# alphanewt_v0_1.net
KiCad netlist of a schematic drawn in EAGLE
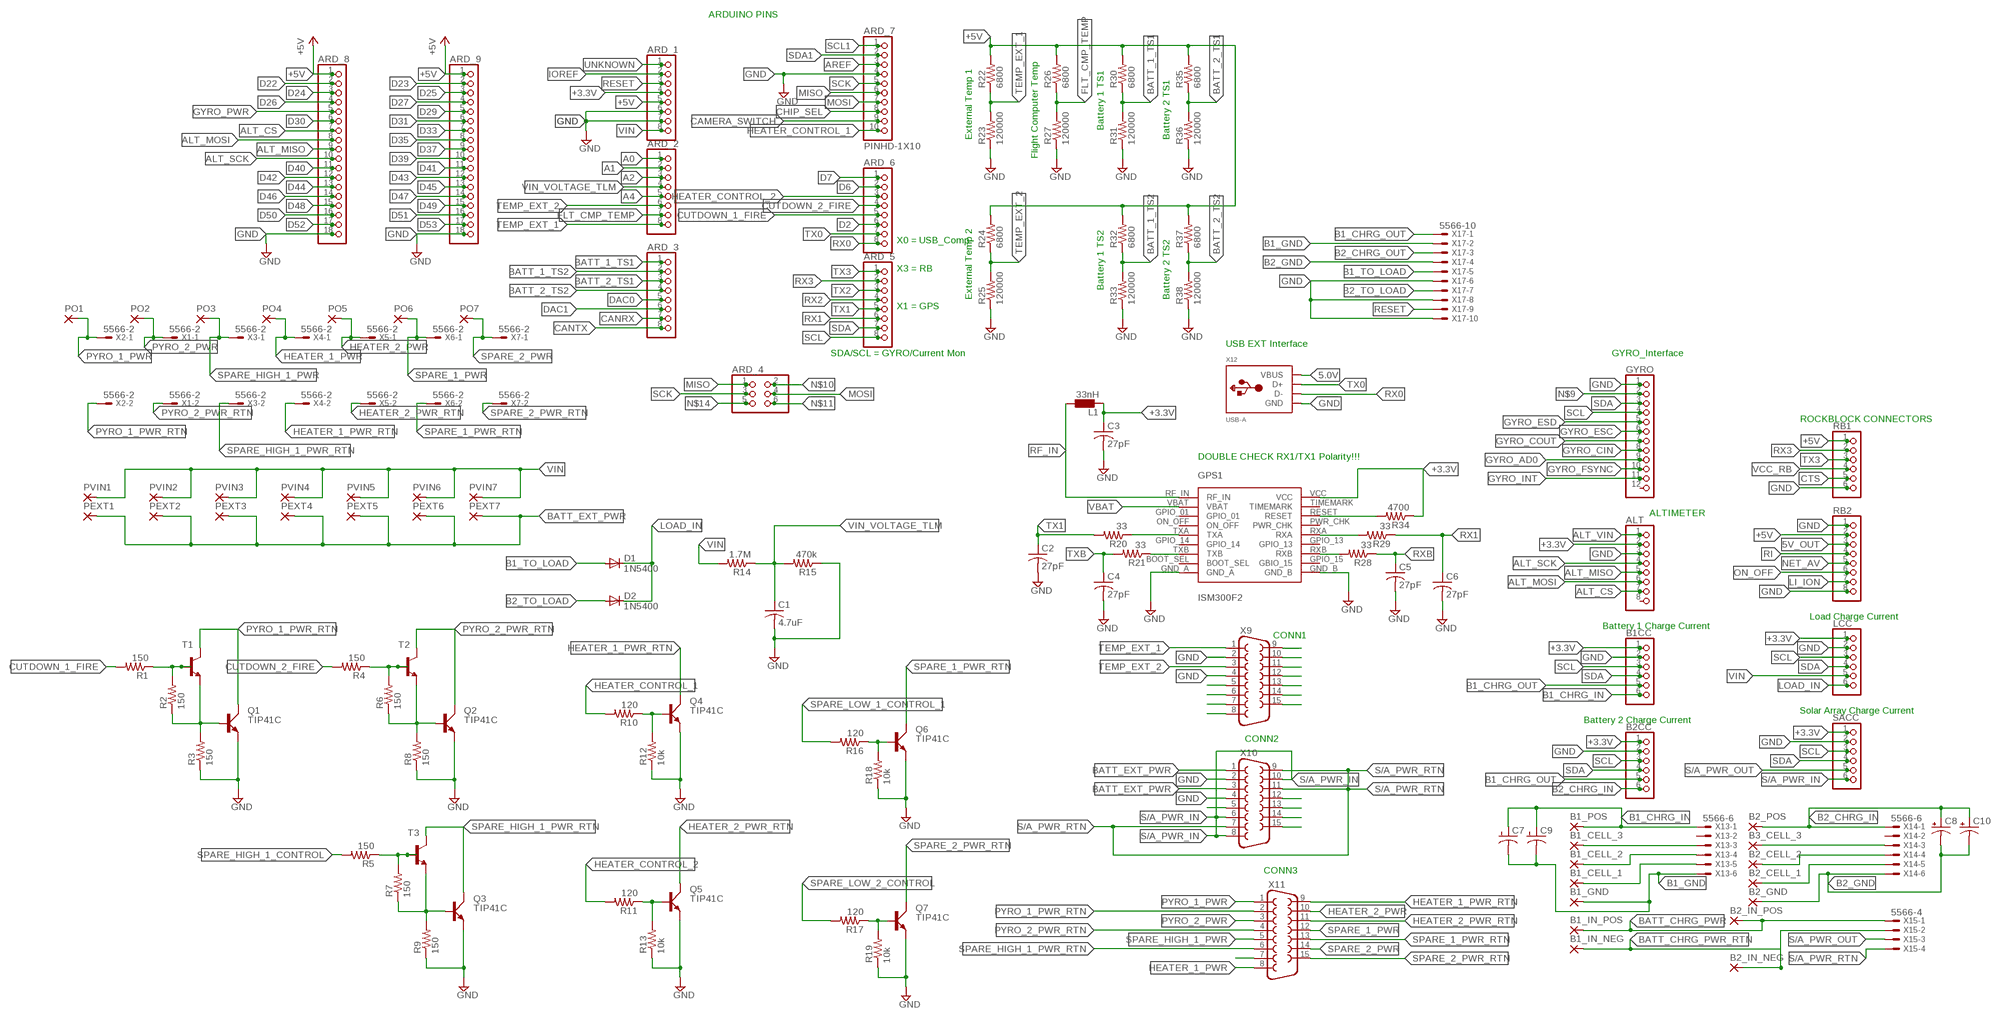
[diagram p0: schematic, sheet 1]

(export (version "E")
  (design (tool "Eeschema 10.0.6"))
  (components
    (comp (ref "ALT")
      (value "PINHD-1X8BIG")
      (footprint "eagle-import:1X08-BIG")
      (libsource (lib "eagle-import") (part "PINHD-1X8BIG"))
    )
    (comp (ref "ARD_1")
      (value "PINHD-1X8BIG")
      (footprint "eagle-import:1X08-BIG")
      (libsource (lib "eagle-import") (part "PINHD-1X8BIG"))
    )
    (comp (ref "ARD_2")
      (value "PINHD-1X8BIG")
      (footprint "eagle-import:1X08-BIG")
      (libsource (lib "eagle-import") (part "PINHD-1X8BIG"))
    )
    (comp (ref "ARD_3")
      (value "PINHD-1X8BIG")
      (footprint "eagle-import:1X08-BIG")
      (libsource (lib "eagle-import") (part "PINHD-1X8BIG"))
    )
    (comp (ref "ARD_4")
      (value "PINHD-2X3")
      (footprint "eagle-import:2X03")
      (libsource (lib "eagle-import") (part "PINHD-2X3"))
    )
    (comp (ref "ARD_5")
      (value "PINHD-1X8BIG")
      (footprint "eagle-import:1X08-BIG")
      (libsource (lib "eagle-import") (part "PINHD-1X8BIG"))
    )
    (comp (ref "ARD_6")
      (value "PINHD-1X8BIG")
      (footprint "eagle-import:1X08-BIG")
      (libsource (lib "eagle-import") (part "PINHD-1X8BIG"))
    )
    (comp (ref "ARD_7")
      (value "PINHD-1X10")
      (footprint "eagle-import:1X10-BIG")
      (libsource (lib "eagle-import") (part "PINHD-1X10"))
    )
    (comp (ref "ARD_8")
      (value "PINHD-1X18-BIG")
      (footprint "eagle-import:1X18-BIG")
      (libsource (lib "eagle-import") (part "PINHD-1X18-BIG"))
    )
    (comp (ref "ARD_9")
      (value "PINHD-1X18-BIG")
      (footprint "eagle-import:1X18-BIG")
      (libsource (lib "eagle-import") (part "PINHD-1X18-BIG"))
    )
    (comp (ref "B1CC")
      (value "PINHD-1X6B")
      (footprint "eagle-import:1X06-BIG")
      (libsource (lib "eagle-import") (part "PINHD-1X6B"))
    )
    (comp (ref "B1_CELL_1")
      (value "SMD5")
      (footprint "eagle-import:SMD2,54-5,08")
      (libsource (lib "eagle-import") (part "SMD5"))
    )
    (comp (ref "B1_CELL_2")
      (value "SMD5")
      (footprint "eagle-import:SMD2,54-5,08")
      (libsource (lib "eagle-import") (part "SMD5"))
    )
    (comp (ref "B1_CELL_3")
      (value "SMD5")
      (footprint "eagle-import:SMD2,54-5,08")
      (libsource (lib "eagle-import") (part "SMD5"))
    )
    (comp (ref "B1_GND")
      (value "SMD5")
      (footprint "eagle-import:SMD2,54-5,08")
      (libsource (lib "eagle-import") (part "SMD5"))
    )
    (comp (ref "B1_IN_NEG")
      (value "SMD5")
      (footprint "eagle-import:SMD2,54-5,08")
      (libsource (lib "eagle-import") (part "SMD5"))
    )
    (comp (ref "B1_IN_POS")
      (value "SMD5")
      (footprint "eagle-import:SMD2,54-5,08")
      (libsource (lib "eagle-import") (part "SMD5"))
    )
    (comp (ref "B1_POS")
      (value "SMD5")
      (footprint "eagle-import:SMD2,54-5,08")
      (libsource (lib "eagle-import") (part "SMD5"))
    )
    (comp (ref "B2CC")
      (value "PINHD-1X6B")
      (footprint "eagle-import:1X06-BIG")
      (libsource (lib "eagle-import") (part "PINHD-1X6B"))
    )
    (comp (ref "B2_CELL_1")
      (value "SMD5")
      (footprint "eagle-import:SMD2,54-5,08")
      (libsource (lib "eagle-import") (part "SMD5"))
    )
    (comp (ref "B2_CELL_2")
      (value "SMD5")
      (footprint "eagle-import:SMD2,54-5,08")
      (libsource (lib "eagle-import") (part "SMD5"))
    )
    (comp (ref "B2_GND")
      (value "SMD5")
      (footprint "eagle-import:SMD2,54-5,08")
      (libsource (lib "eagle-import") (part "SMD5"))
    )
    (comp (ref "B2_IN_NEG")
      (value "SMD5")
      (footprint "eagle-import:SMD2,54-5,08")
      (libsource (lib "eagle-import") (part "SMD5"))
    )
    (comp (ref "B2_IN_POS")
      (value "SMD5")
      (footprint "eagle-import:SMD2,54-5,08")
      (libsource (lib "eagle-import") (part "SMD5"))
    )
    (comp (ref "B2_POS")
      (value "SMD5")
      (footprint "eagle-import:SMD2,54-5,08")
      (libsource (lib "eagle-import") (part "SMD5"))
    )
    (comp (ref "B3_CELL_3")
      (value "SMD5")
      (footprint "eagle-import:SMD2,54-5,08")
      (libsource (lib "eagle-import") (part "SMD5"))
    )
    (comp (ref "C1")
      (value "4.7uF")
      (footprint "eagle-import:C0805K")
      (fields (field (name "MPN") "C0805C270J5GACTU"))
      (libsource (lib "eagle-import") (part "C-USC0805K"))
    )
    (comp (ref "C2")
      (value "27pF")
      (footprint "eagle-import:C0805K")
      (fields (field (name "MPN") "C0805C270J5GACTU"))
      (libsource (lib "eagle-import") (part "C-USC0805K"))
    )
    (comp (ref "C3")
      (value "27pF")
      (footprint "eagle-import:C0805K")
      (fields (field (name "MPN") "C0805C270J5GACTU"))
      (libsource (lib "eagle-import") (part "C-USC0805K"))
    )
    (comp (ref "C4")
      (value "27pF")
      (footprint "eagle-import:C0805K")
      (fields (field (name "MPN") "C0805C270J5GACTU"))
      (libsource (lib "eagle-import") (part "C-USC0805K"))
    )
    (comp (ref "C5")
      (value "27pF")
      (footprint "eagle-import:C0805K")
      (fields (field (name "MPN") "C0805C270J5GACTU"))
      (libsource (lib "eagle-import") (part "C-USC0805K"))
    )
    (comp (ref "C6")
      (value "27pF")
      (footprint "eagle-import:C0805K")
      (fields (field (name "MPN") "C0805C270J5GACTU"))
      (libsource (lib "eagle-import") (part "C-USC0805K"))
    )
    (comp (ref "C7")
      (value "CPOL-USCT7343")
      (footprint "eagle-import:CT7343")
      (libsource (lib "eagle-import") (part "CPOL-USCT7343"))
    )
    (comp (ref "C8")
      (value "CPOL-USCT7343")
      (footprint "eagle-import:CT7343")
      (libsource (lib "eagle-import") (part "CPOL-USCT7343"))
    )
    (comp (ref "C9")
      (value "CPOL-USCT7343")
      (footprint "eagle-import:CT7343")
      (libsource (lib "eagle-import") (part "CPOL-USCT7343"))
    )
    (comp (ref "C10")
      (value "CPOL-USCT7343")
      (footprint "eagle-import:CT7343")
      (libsource (lib "eagle-import") (part "CPOL-USCT7343"))
    )
    (comp (ref "D1")
      (value "1N5400")
      (footprint "eagle-import:DO201-15")
      (libsource (lib "eagle-import") (part "1N5400"))
    )
    (comp (ref "D2")
      (value "1N5400")
      (footprint "eagle-import:DO201-15")
      (libsource (lib "eagle-import") (part "1N5400"))
    )
    (comp (ref "GPS1")
      (value "ISM300F2")
      (footprint "eagle-import:ISM300F2")
      (libsource (lib "eagle-import") (part "ISM300F2"))
    )
    (comp (ref "GYRO")
      (value "PINHD-1X12-CB")
      (footprint "eagle-import:1X12-CB")
      (libsource (lib "eagle-import") (part "PINHD-1X12-CB"))
    )
    (comp (ref "L1")
      (value "33nH")
      (footprint "eagle-import:L4532P")
      (fields (field (name "MPN") "MCWL06KT33N"))
      (libsource (lib "eagle-import") (part "LL4532P"))
    )
    (comp (ref "LCC")
      (value "PINHD-1X6B")
      (footprint "eagle-import:1X06-BIG")
      (libsource (lib "eagle-import") (part "PINHD-1X6B"))
    )
    (comp (ref "PEXT1")
      (value "SMD2")
      (footprint "eagle-import:SMD1,27-2,54")
      (libsource (lib "eagle-import") (part "SMD2"))
    )
    (comp (ref "PEXT2")
      (value "SMD2")
      (footprint "eagle-import:SMD1,27-2,54")
      (libsource (lib "eagle-import") (part "SMD2"))
    )
    (comp (ref "PEXT3")
      (value "SMD2")
      (footprint "eagle-import:SMD1,27-2,54")
      (libsource (lib "eagle-import") (part "SMD2"))
    )
    (comp (ref "PEXT4")
      (value "SMD2")
      (footprint "eagle-import:SMD1,27-2,54")
      (libsource (lib "eagle-import") (part "SMD2"))
    )
    (comp (ref "PEXT5")
      (value "SMD2")
      (footprint "eagle-import:SMD1,27-2,54")
      (libsource (lib "eagle-import") (part "SMD2"))
    )
    (comp (ref "PEXT6")
      (value "SMD2")
      (footprint "eagle-import:SMD1,27-2,54")
      (libsource (lib "eagle-import") (part "SMD2"))
    )
    (comp (ref "PEXT7")
      (value "SMD2")
      (footprint "eagle-import:SMD1,27-2,54")
      (libsource (lib "eagle-import") (part "SMD2"))
    )
    (comp (ref "PO1")
      (value "SMD2")
      (footprint "eagle-import:SMD1,27-2,54")
      (libsource (lib "eagle-import") (part "SMD2"))
    )
    (comp (ref "PO2")
      (value "SMD2")
      (footprint "eagle-import:SMD1,27-2,54")
      (libsource (lib "eagle-import") (part "SMD2"))
    )
    (comp (ref "PO3")
      (value "SMD2")
      (footprint "eagle-import:SMD1,27-2,54")
      (libsource (lib "eagle-import") (part "SMD2"))
    )
    (comp (ref "PO4")
      (value "SMD2")
      (footprint "eagle-import:SMD1,27-2,54")
      (libsource (lib "eagle-import") (part "SMD2"))
    )
    (comp (ref "PO5")
      (value "SMD2")
      (footprint "eagle-import:SMD1,27-2,54")
      (libsource (lib "eagle-import") (part "SMD2"))
    )
    (comp (ref "PO6")
      (value "SMD2")
      (footprint "eagle-import:SMD1,27-2,54")
      (libsource (lib "eagle-import") (part "SMD2"))
    )
    (comp (ref "PO7")
      (value "SMD2")
      (footprint "eagle-import:SMD1,27-2,54")
      (libsource (lib "eagle-import") (part "SMD2"))
    )
    (comp (ref "PVIN1")
      (value "SMD2")
      (footprint "eagle-import:SMD1,27-2,54")
      (libsource (lib "eagle-import") (part "SMD2"))
    )
    (comp (ref "PVIN2")
      (value "SMD2")
      (footprint "eagle-import:SMD1,27-2,54")
      (libsource (lib "eagle-import") (part "SMD2"))
    )
    (comp (ref "PVIN3")
      (value "SMD2")
      (footprint "eagle-import:SMD1,27-2,54")
      (libsource (lib "eagle-import") (part "SMD2"))
    )
    (comp (ref "PVIN4")
      (value "SMD2")
      (footprint "eagle-import:SMD1,27-2,54")
      (libsource (lib "eagle-import") (part "SMD2"))
    )
    (comp (ref "PVIN5")
      (value "SMD2")
      (footprint "eagle-import:SMD1,27-2,54")
      (libsource (lib "eagle-import") (part "SMD2"))
    )
    (comp (ref "PVIN6")
      (value "SMD2")
      (footprint "eagle-import:SMD1,27-2,54")
      (libsource (lib "eagle-import") (part "SMD2"))
    )
    (comp (ref "PVIN7")
      (value "SMD2")
      (footprint "eagle-import:SMD1,27-2,54")
      (libsource (lib "eagle-import") (part "SMD2"))
    )
    (comp (ref "Q1")
      (value "TIP41C")
      (footprint "eagle-import:TO220AV")
      (libsource (lib "eagle-import") (part "TIP41C"))
    )
    (comp (ref "Q2")
      (value "TIP41C")
      (footprint "eagle-import:TO220AV")
      (libsource (lib "eagle-import") (part "TIP41C"))
    )
    (comp (ref "Q3")
      (value "TIP41C")
      (footprint "eagle-import:TO220AV")
      (libsource (lib "eagle-import") (part "TIP41C"))
    )
    (comp (ref "Q4")
      (value "TIP41C")
      (footprint "eagle-import:TO220AV")
      (libsource (lib "eagle-import") (part "TIP41C"))
    )
    (comp (ref "Q5")
      (value "TIP41C")
      (footprint "eagle-import:TO220AV")
      (libsource (lib "eagle-import") (part "TIP41C"))
    )
    (comp (ref "Q6")
      (value "TIP41C")
      (footprint "eagle-import:TO220AV")
      (libsource (lib "eagle-import") (part "TIP41C"))
    )
    (comp (ref "Q7")
      (value "TIP41C")
      (footprint "eagle-import:TO220AV")
      (libsource (lib "eagle-import") (part "TIP41C"))
    )
    (comp (ref "R1")
      (value "150")
      (footprint "eagle-import:R0805")
      (fields (field (name "MF") "VISHAY/DALE") (field (name "MPN") "CRCW120633R2FKEA"))
      (libsource (lib "eagle-import") (part "R-US_R0805"))
    )
    (comp (ref "R2")
      (value "150")
      (footprint "eagle-import:R0805")
      (fields (field (name "MF") "VISHAY/DALE") (field (name "MPN") "CRCW120633R2FKEA"))
      (libsource (lib "eagle-import") (part "R-US_R0805"))
    )
    (comp (ref "R3")
      (value "150")
      (footprint "eagle-import:R0805")
      (fields (field (name "MF") "VISHAY/DALE") (field (name "MPN") "CRCW120633R2FKEA"))
      (libsource (lib "eagle-import") (part "R-US_R0805"))
    )
    (comp (ref "R4")
      (value "150")
      (footprint "eagle-import:R0805")
      (fields (field (name "MF") "VISHAY/DALE") (field (name "MPN") "CRCW120633R2FKEA"))
      (libsource (lib "eagle-import") (part "R-US_R0805"))
    )
    (comp (ref "R5")
      (value "150")
      (footprint "eagle-import:R0805")
      (fields (field (name "MF") "VISHAY/DALE") (field (name "MPN") "CRCW120633R2FKEA"))
      (libsource (lib "eagle-import") (part "R-US_R0805"))
    )
    (comp (ref "R6")
      (value "150")
      (footprint "eagle-import:R0805")
      (fields (field (name "MF") "VISHAY/DALE") (field (name "MPN") "CRCW120633R2FKEA"))
      (libsource (lib "eagle-import") (part "R-US_R0805"))
    )
    (comp (ref "R7")
      (value "150")
      (footprint "eagle-import:R0805")
      (fields (field (name "MF") "VISHAY/DALE") (field (name "MPN") "CRCW120633R2FKEA"))
      (libsource (lib "eagle-import") (part "R-US_R0805"))
    )
    (comp (ref "R8")
      (value "150")
      (footprint "eagle-import:R0805")
      (fields (field (name "MF") "VISHAY/DALE") (field (name "MPN") "CRCW120633R2FKEA"))
      (libsource (lib "eagle-import") (part "R-US_R0805"))
    )
    (comp (ref "R9")
      (value "150")
      (footprint "eagle-import:R0805")
      (fields (field (name "MF") "VISHAY/DALE") (field (name "MPN") "CRCW120633R2FKEA"))
      (libsource (lib "eagle-import") (part "R-US_R0805"))
    )
    (comp (ref "R10")
      (value "120")
      (footprint "eagle-import:R0805")
      (fields (field (name "MF") "VISHAY/DALE") (field (name "MPN") "CRCW120633R2FKEA"))
      (libsource (lib "eagle-import") (part "R-US_R0805"))
    )
    (comp (ref "R11")
      (value "120")
      (footprint "eagle-import:R0805")
      (fields (field (name "MF") "VISHAY/DALE") (field (name "MPN") "CRCW120633R2FKEA"))
      (libsource (lib "eagle-import") (part "R-US_R0805"))
    )
    (comp (ref "R12")
      (value "10k")
      (footprint "eagle-import:R0805")
      (fields (field (name "MF") "VISHAY/DALE") (field (name "MPN") "CRCW120633R2FKEA"))
      (libsource (lib "eagle-import") (part "R-US_R0805"))
    )
    (comp (ref "R13")
      (value "10k")
      (footprint "eagle-import:R0805")
      (fields (field (name "MF") "VISHAY/DALE") (field (name "MPN") "CRCW120633R2FKEA"))
      (libsource (lib "eagle-import") (part "R-US_R0805"))
    )
    (comp (ref "R14")
      (value "1.7M")
      (footprint "eagle-import:R0805")
      (fields (field (name "MF") "VISHAY/DALE") (field (name "MPN") "CRCW120633R2FKEA"))
      (libsource (lib "eagle-import") (part "R-US_R0805"))
    )
    (comp (ref "R15")
      (value "470k")
      (footprint "eagle-import:R0805")
      (fields (field (name "MF") "VISHAY/DALE") (field (name "MPN") "CRCW120633R2FKEA"))
      (libsource (lib "eagle-import") (part "R-US_R0805"))
    )
    (comp (ref "R16")
      (value "120")
      (footprint "eagle-import:R0805")
      (fields (field (name "MF") "VISHAY/DALE") (field (name "MPN") "CRCW120633R2FKEA"))
      (libsource (lib "eagle-import") (part "R-US_R0805"))
    )
    (comp (ref "R17")
      (value "120")
      (footprint "eagle-import:R0805")
      (fields (field (name "MF") "VISHAY/DALE") (field (name "MPN") "CRCW120633R2FKEA"))
      (libsource (lib "eagle-import") (part "R-US_R0805"))
    )
    (comp (ref "R18")
      (value "10k")
      (footprint "eagle-import:R0805")
      (fields (field (name "MF") "VISHAY/DALE") (field (name "MPN") "CRCW120633R2FKEA"))
      (libsource (lib "eagle-import") (part "R-US_R0805"))
    )
    (comp (ref "R19")
      (value "10k")
      (footprint "eagle-import:R0805")
      (fields (field (name "MF") "VISHAY/DALE") (field (name "MPN") "CRCW120633R2FKEA"))
      (libsource (lib "eagle-import") (part "R-US_R0805"))
    )
    (comp (ref "R20")
      (value "33")
      (footprint "eagle-import:R0805")
      (fields (field (name "MF") "VISHAY/DALE") (field (name "MPN") "CRCW120633R2FKEA"))
      (libsource (lib "eagle-import") (part "R-US_R0805"))
    )
    (comp (ref "R21")
      (value "33")
      (footprint "eagle-import:R0805")
      (fields (field (name "MF") "VISHAY/DALE") (field (name "MPN") "CRCW120633R2FKEA"))
      (libsource (lib "eagle-import") (part "R-US_R0805"))
    )
    (comp (ref "R22")
      (value "6800")
      (footprint "eagle-import:R0805")
      (fields (field (name "MF") "VISHAY/DALE") (field (name "MPN") "CRCW120633R2FKEA"))
      (libsource (lib "eagle-import") (part "R-US_R0805"))
    )
    (comp (ref "R23")
      (value "120000")
      (footprint "eagle-import:R0805")
      (fields (field (name "MF") "VISHAY/DALE") (field (name "MPN") "CRCW120633R2FKEA"))
      (libsource (lib "eagle-import") (part "R-US_R0805"))
    )
    (comp (ref "R24")
      (value "6800")
      (footprint "eagle-import:R0805")
      (fields (field (name "MF") "VISHAY/DALE") (field (name "MPN") "CRCW120633R2FKEA"))
      (libsource (lib "eagle-import") (part "R-US_R0805"))
    )
    (comp (ref "R25")
      (value "120000")
      (footprint "eagle-import:R0805")
      (fields (field (name "MF") "VISHAY/DALE") (field (name "MPN") "CRCW120633R2FKEA"))
      (libsource (lib "eagle-import") (part "R-US_R0805"))
    )
    (comp (ref "R26")
      (value "6800")
      (footprint "eagle-import:R0805")
      (fields (field (name "MF") "VISHAY/DALE") (field (name "MPN") "CRCW120633R2FKEA"))
      (libsource (lib "eagle-import") (part "R-US_R0805"))
    )
    (comp (ref "R27")
      (value "120000")
      (footprint "eagle-import:R0805")
      (fields (field (name "MF") "VISHAY/DALE") (field (name "MPN") "CRCW120633R2FKEA"))
      (libsource (lib "eagle-import") (part "R-US_R0805"))
    )
    (comp (ref "R28")
      (value "33")
      (footprint "eagle-import:R0805")
      (fields (field (name "MF") "VISHAY/DALE") (field (name "MPN") "CRCW120633R2FKEA"))
      (libsource (lib "eagle-import") (part "R-US_R0805"))
    )
    (comp (ref "R29")
      (value "33")
      (footprint "eagle-import:R0805")
      (fields (field (name "MF") "VISHAY/DALE") (field (name "MPN") "CRCW120633R2FKEA"))
      (libsource (lib "eagle-import") (part "R-US_R0805"))
    )
    (comp (ref "R30")
      (value "6800")
      (footprint "eagle-import:R0805")
      (fields (field (name "MF") "VISHAY/DALE") (field (name "MPN") "CRCW120633R2FKEA"))
      (libsource (lib "eagle-import") (part "R-US_R0805"))
    )
    (comp (ref "R31")
      (value "120000")
      (footprint "eagle-import:R0805")
      (fields (field (name "MF") "VISHAY/DALE") (field (name "MPN") "CRCW120633R2FKEA"))
      (libsource (lib "eagle-import") (part "R-US_R0805"))
    )
    (comp (ref "R32")
      (value "6800")
      (footprint "eagle-import:R0805")
      (fields (field (name "MF") "VISHAY/DALE") (field (name "MPN") "CRCW120633R2FKEA"))
      (libsource (lib "eagle-import") (part "R-US_R0805"))
    )
    (comp (ref "R33")
      (value "120000")
      (footprint "eagle-import:R0805")
      (fields (field (name "MF") "VISHAY/DALE") (field (name "MPN") "CRCW120633R2FKEA"))
      (libsource (lib "eagle-import") (part "R-US_R0805"))
    )
    (comp (ref "R34")
      (value "4700")
      (footprint "eagle-import:R0805")
      (fields (field (name "MF") "VISHAY/DALE") (field (name "MPN") "CRCW12104K70FKEA"))
      (libsource (lib "eagle-import") (part "R-US_R0805"))
    )
    (comp (ref "R35")
      (value "6800")
      (footprint "eagle-import:R0805")
      (fields (field (name "MF") "VISHAY/DALE") (field (name "MPN") "CRCW120633R2FKEA"))
      (libsource (lib "eagle-import") (part "R-US_R0805"))
    )
    (comp (ref "R36")
      (value "120000")
      (footprint "eagle-import:R0805")
      (fields (field (name "MF") "VISHAY/DALE") (field (name "MPN") "CRCW120633R2FKEA"))
      (libsource (lib "eagle-import") (part "R-US_R0805"))
    )
    (comp (ref "R37")
      (value "6800")
      (footprint "eagle-import:R0805")
      (fields (field (name "MF") "VISHAY/DALE") (field (name "MPN") "CRCW120633R2FKEA"))
      (libsource (lib "eagle-import") (part "R-US_R0805"))
    )
    (comp (ref "R38")
      (value "120000")
      (footprint "eagle-import:R0805")
      (fields (field (name "MF") "VISHAY/DALE") (field (name "MPN") "CRCW120633R2FKEA"))
      (libsource (lib "eagle-import") (part "R-US_R0805"))
    )
    (comp (ref "RB1")
      (value "PINHD-1X6CB")
      (footprint "eagle-import:1X06-CLEANBIG")
      (libsource (lib "eagle-import") (part "PINHD-1X6CB"))
    )
    (comp (ref "RB2")
      (value "PINHD-1X8BIG")
      (footprint "eagle-import:1X08-BIG")
      (libsource (lib "eagle-import") (part "PINHD-1X8BIG"))
    )
    (comp (ref "SACC")
      (value "PINHD-1X6B")
      (footprint "eagle-import:1X06-BIG")
      (libsource (lib "eagle-import") (part "PINHD-1X6B"))
    )
    (comp (ref "T1")
      (value "2N3904")
      (footprint "eagle-import:TO92")
      (libsource (lib "eagle-import") (part "2N3904"))
    )
    (comp (ref "T2")
      (value "2N3904")
      (footprint "eagle-import:TO92")
      (libsource (lib "eagle-import") (part "2N3904"))
    )
    (comp (ref "T3")
      (value "2N3904")
      (footprint "eagle-import:TO92")
      (libsource (lib "eagle-import") (part "2N3904"))
    )
    (comp (ref "X1")
      (value "5566-2")
      (footprint "eagle-import:5566-2")
      (libsource (lib "eagle-import") (part "5566-2"))
    )
    (comp (ref "X2")
      (value "5566-2")
      (footprint "eagle-import:5566-2")
      (libsource (lib "eagle-import") (part "5566-2"))
    )
    (comp (ref "X3")
      (value "5566-2")
      (footprint "eagle-import:5566-2")
      (libsource (lib "eagle-import") (part "5566-2"))
    )
    (comp (ref "X4")
      (value "5566-2")
      (footprint "eagle-import:5566-2")
      (libsource (lib "eagle-import") (part "5566-2"))
    )
    (comp (ref "X5")
      (value "5566-2")
      (footprint "eagle-import:5566-2")
      (libsource (lib "eagle-import") (part "5566-2"))
    )
    (comp (ref "X6")
      (value "5566-2")
      (footprint "eagle-import:5566-2")
      (libsource (lib "eagle-import") (part "5566-2"))
    )
    (comp (ref "X7")
      (value "5566-2")
      (footprint "eagle-import:5566-2")
      (libsource (lib "eagle-import") (part "5566-2"))
    )
    (comp (ref "X9")
      (value "F15HP")
      (footprint "eagle-import:F15HP")
      (libsource (lib "eagle-import") (part "F15HP"))
    )
    (comp (ref "X10")
      (value "F15HP")
      (footprint "eagle-import:F15HP")
      (libsource (lib "eagle-import") (part "F15HP"))
    )
    (comp (ref "X11")
      (value "F15HP")
      (footprint "eagle-import:F15HP")
      (libsource (lib "eagle-import") (part "F15HP"))
    )
    (comp (ref "X12")
      (value "USB-A")
      (footprint "eagle-import:MOLEX_480371000")
      (libsource (lib "eagle-import") (part "USB-A"))
    )
    (comp (ref "X13")
      (value "5566-6")
      (footprint "eagle-import:5566-6")
      (fields (field (name "MPN") "95566-61002"))
      (libsource (lib "eagle-import") (part "5566-6"))
    )
    (comp (ref "X14")
      (value "5566-6")
      (footprint "eagle-import:5566-6")
      (fields (field (name "MPN") "95566-61002"))
      (libsource (lib "eagle-import") (part "5566-6"))
    )
    (comp (ref "X15")
      (value "5566-4")
      (footprint "eagle-import:5566-4")
      (libsource (lib "eagle-import") (part "5566-4"))
    )
    (comp (ref "X17")
      (value "5566-10")
      (footprint "eagle-import:5566-10")
      (libsource (lib "eagle-import") (part "5566-10"))
    )
  )
  (nets
    (net (code "1") (name "+3.3V") (class "Default")
      (node (ref "ALT") (pin "2") (pinfunction "2_2") (pintype "passive"))
      (node (ref "ARD_1") (pin "4") (pinfunction "4_4") (pintype "passive"))
      (node (ref "B1CC") (pin "1") (pinfunction "1_1") (pintype "passive"))
      (node (ref "B2CC") (pin "1") (pinfunction "1_1") (pintype "passive"))
      (node (ref "C3") (pin "1") (pinfunction "1_1") (pintype "passive"))
      (node (ref "GPS1") (pin "VCC") (pinfunction "VCC_VCC") (pintype "bidirectional"))
      (node (ref "L1") (pin "2") (pinfunction "2_2") (pintype "passive"))
      (node (ref "LCC") (pin "1") (pinfunction "1_1") (pintype "passive"))
      (node (ref "R34") (pin "1") (pinfunction "1_1") (pintype "passive"))
      (node (ref "SACC") (pin "1") (pinfunction "1_1") (pintype "passive"))
    )
    (net (code "2") (name "+5V") (class "Default")
      (node (ref "ARD_1") (pin "5") (pinfunction "5_5") (pintype "passive"))
      (node (ref "ARD_8") (pin "1") (pinfunction "1_1") (pintype "passive"))
      (node (ref "ARD_9") (pin "1") (pinfunction "1_1") (pintype "passive"))
      (node (ref "R22") (pin "2") (pinfunction "2_2") (pintype "passive"))
      (node (ref "R24") (pin "2") (pinfunction "2_2") (pintype "passive"))
      (node (ref "R26") (pin "2") (pinfunction "2_2") (pintype "passive"))
      (node (ref "R30") (pin "2") (pinfunction "2_2") (pintype "passive"))
      (node (ref "R32") (pin "2") (pinfunction "2_2") (pintype "passive"))
      (node (ref "R35") (pin "2") (pinfunction "2_2") (pintype "passive"))
      (node (ref "R37") (pin "2") (pinfunction "2_2") (pintype "passive"))
      (node (ref "RB1") (pin "1") (pinfunction "1_1") (pintype "passive"))
      (node (ref "RB2") (pin "2") (pinfunction "2_2") (pintype "passive"))
    )
    (net (code "3") (name "5.0V") (class "Default")
      (node (ref "X12") (pin "1") (pinfunction "VBUS_1") (pintype "power_in"))
    )
    (net (code "4") (name "5V_OUT") (class "Default")
      (node (ref "RB2") (pin "3") (pinfunction "3_3") (pintype "passive"))
    )
    (net (code "5") (name "A0") (class "Default")
      (node (ref "ARD_2") (pin "1") (pinfunction "1_1") (pintype "passive"))
    )
    (net (code "6") (name "A1") (class "Default")
      (node (ref "ARD_2") (pin "2") (pinfunction "2_2") (pintype "passive"))
    )
    (net (code "7") (name "A2") (class "Default")
      (node (ref "ARD_2") (pin "3") (pinfunction "3_3") (pintype "passive"))
    )
    (net (code "8") (name "A4") (class "Default")
      (node (ref "ARD_2") (pin "5") (pinfunction "5_5") (pintype "passive"))
    )
    (net (code "9") (name "ALT_CS") (class "Default")
      (node (ref "ALT") (pin "7") (pinfunction "7_7") (pintype "passive"))
      (node (ref "ARD_8") (pin "7") (pinfunction "7_7") (pintype "passive"))
    )
    (net (code "10") (name "ALT_MISO") (class "Default")
      (node (ref "ALT") (pin "5") (pinfunction "5_5") (pintype "passive"))
      (node (ref "ARD_8") (pin "9") (pinfunction "9_9") (pintype "passive"))
    )
    (net (code "11") (name "ALT_MOSI") (class "Default")
      (node (ref "ALT") (pin "6") (pinfunction "6_6") (pintype "passive"))
      (node (ref "ARD_8") (pin "8") (pinfunction "8_8") (pintype "passive"))
    )
    (net (code "12") (name "ALT_SCK") (class "Default")
      (node (ref "ALT") (pin "4") (pinfunction "4_4") (pintype "passive"))
      (node (ref "ARD_8") (pin "10") (pinfunction "10_10") (pintype "passive"))
    )
    (net (code "13") (name "ALT_VIN") (class "Default")
      (node (ref "ALT") (pin "1") (pinfunction "1_1") (pintype "passive"))
    )
    (net (code "14") (name "AREF") (class "Default")
      (node (ref "ARD_7") (pin "3") (pinfunction "3_3") (pintype "passive"))
    )
    (net (code "15") (name "B1_CHRG_IN") (class "Default")
      (node (ref "B1CC") (pin "6") (pinfunction "6_6") (pintype "passive"))
      (node (ref "B1_POS") (pin "1") (pinfunction "P_1") (pintype "passive"))
      (node (ref "C7") (pin "+") (pinfunction "+_+") (pintype "passive"))
      (node (ref "C9") (pin "+") (pinfunction "+_+") (pintype "passive"))
      (node (ref "X13") (pin "1") (pinfunction "S_1") (pintype "passive"))
    )
    (net (code "16") (name "B1_CHRG_OUT") (class "Default")
      (node (ref "B1CC") (pin "5") (pinfunction "5_5") (pintype "passive"))
      (node (ref "B2CC") (pin "5") (pinfunction "5_5") (pintype "passive"))
      (node (ref "X17") (pin "1") (pinfunction "S_1") (pintype "passive"))
    )
    (net (code "17") (name "B1_GND") (class "Default")
      (node (ref "B1_GND") (pin "1") (pinfunction "P_1") (pintype "passive"))
      (node (ref "C7") (pin "-") (pinfunction "-_-") (pintype "passive"))
      (node (ref "C9") (pin "-") (pinfunction "-_-") (pintype "passive"))
      (node (ref "X13") (pin "6") (pinfunction "S_6") (pintype "passive"))
      (node (ref "X17") (pin "2") (pinfunction "S_2") (pintype "passive"))
    )
    (net (code "18") (name "B1_TO_LOAD") (class "Default")
      (node (ref "D1") (pin "A") (pinfunction "A_A") (pintype "passive"))
      (node (ref "X17") (pin "5") (pinfunction "S_5") (pintype "passive"))
    )
    (net (code "19") (name "B2_CHRG_IN") (class "Default")
      (node (ref "B2CC") (pin "6") (pinfunction "6_6") (pintype "passive"))
      (node (ref "B2_POS") (pin "1") (pinfunction "P_1") (pintype "passive"))
      (node (ref "C10") (pin "+") (pinfunction "+_+") (pintype "passive"))
      (node (ref "C8") (pin "+") (pinfunction "+_+") (pintype "passive"))
      (node (ref "X14") (pin "1") (pinfunction "S_1") (pintype "passive"))
    )
    (net (code "20") (name "B2_CHRG_OUT") (class "Default")
      (node (ref "X17") (pin "3") (pinfunction "S_3") (pintype "passive"))
    )
    (net (code "21") (name "B2_GND") (class "Default")
      (node (ref "B2_GND") (pin "1") (pinfunction "P_1") (pintype "passive"))
      (node (ref "C10") (pin "-") (pinfunction "-_-") (pintype "passive"))
      (node (ref "C8") (pin "-") (pinfunction "-_-") (pintype "passive"))
      (node (ref "X14") (pin "6") (pinfunction "S_6") (pintype "passive"))
      (node (ref "X17") (pin "4") (pinfunction "S_4") (pintype "passive"))
    )
    (net (code "22") (name "B2_TO_LOAD") (class "Default")
      (node (ref "D2") (pin "A") (pinfunction "A_A") (pintype "passive"))
      (node (ref "X17") (pin "7") (pinfunction "S_7") (pintype "passive"))
    )
    (net (code "23") (name "BATT_1_TS1") (class "Default")
      (node (ref "ARD_3") (pin "1") (pinfunction "1_1") (pintype "passive"))
      (node (ref "R30") (pin "1") (pinfunction "1_1") (pintype "passive"))
      (node (ref "R31") (pin "2") (pinfunction "2_2") (pintype "passive"))
    )
    (net (code "24") (name "BATT_1_TS2") (class "Default")
      (node (ref "ARD_3") (pin "2") (pinfunction "2_2") (pintype "passive"))
      (node (ref "R32") (pin "1") (pinfunction "1_1") (pintype "passive"))
      (node (ref "R33") (pin "2") (pinfunction "2_2") (pintype "passive"))
    )
    (net (code "25") (name "BATT_2_TS1") (class "Default")
      (node (ref "ARD_3") (pin "3") (pinfunction "3_3") (pintype "passive"))
      (node (ref "R35") (pin "1") (pinfunction "1_1") (pintype "passive"))
      (node (ref "R36") (pin "2") (pinfunction "2_2") (pintype "passive"))
    )
    (net (code "26") (name "BATT_2_TS2") (class "Default")
      (node (ref "ARD_3") (pin "4") (pinfunction "4_4") (pintype "passive"))
      (node (ref "R37") (pin "1") (pinfunction "1_1") (pintype "passive"))
      (node (ref "R38") (pin "2") (pinfunction "2_2") (pintype "passive"))
    )
    (net (code "27") (name "BATT_CHRG_PWR") (class "Default")
      (node (ref "B1_IN_POS") (pin "1") (pinfunction "P_1") (pintype "passive"))
      (node (ref "B2_IN_POS") (pin "1") (pinfunction "P_1") (pintype "passive"))
      (node (ref "X15") (pin "1") (pinfunction "S_1") (pintype "passive"))
    )
    (net (code "28") (name "BATT_CHRG_PWR_RTN") (class "Default")
      (node (ref "B1_IN_NEG") (pin "1") (pinfunction "P_1") (pintype "passive"))
      (node (ref "B2_IN_NEG") (pin "1") (pinfunction "P_1") (pintype "passive"))
      (node (ref "X15") (pin "2") (pinfunction "S_2") (pintype "passive"))
    )
    (net (code "29") (name "BATT_EXT_PWR") (class "Default")
      (node (ref "PEXT1") (pin "1") (pinfunction "P_1") (pintype "passive"))
      (node (ref "PEXT2") (pin "1") (pinfunction "P_1") (pintype "passive"))
      (node (ref "PEXT3") (pin "1") (pinfunction "P_1") (pintype "passive"))
      (node (ref "PEXT4") (pin "1") (pinfunction "P_1") (pintype "passive"))
      (node (ref "PEXT5") (pin "1") (pinfunction "P_1") (pintype "passive"))
      (node (ref "PEXT6") (pin "1") (pinfunction "P_1") (pintype "passive"))
      (node (ref "PEXT7") (pin "1") (pinfunction "P_1") (pintype "passive"))
      (node (ref "X10") (pin "1") (pinfunction "1_1") (pintype "passive"))
      (node (ref "X10") (pin "3") (pinfunction "3_3") (pintype "passive"))
    )
    (net (code "30") (name "CAMERA_SWITCH") (class "Default")
      (node (ref "ARD_7") (pin "9") (pinfunction "9_9") (pintype "passive"))
    )
    (net (code "31") (name "CANRX") (class "Default")
      (node (ref "ARD_3") (pin "7") (pinfunction "7_7") (pintype "passive"))
    )
    (net (code "32") (name "CANTX") (class "Default")
      (node (ref "ARD_3") (pin "8") (pinfunction "8_8") (pintype "passive"))
    )
    (net (code "33") (name "CHIP_SEL") (class "Default")
      (node (ref "ARD_7") (pin "8") (pinfunction "8_8") (pintype "passive"))
    )
    (net (code "34") (name "CTS") (class "Default")
      (node (ref "RB1") (pin "5") (pinfunction "5_5") (pintype "passive"))
    )
    (net (code "35") (name "CUTDOWN_1_FIRE") (class "Default")
      (node (ref "ARD_6") (pin "5") (pinfunction "5_5") (pintype "passive"))
      (node (ref "R1") (pin "2") (pinfunction "2_2") (pintype "passive"))
    )
    (net (code "36") (name "CUTDOWN_2_FIRE") (class "Default")
      (node (ref "ARD_6") (pin "4") (pinfunction "4_4") (pintype "passive"))
      (node (ref "R4") (pin "2") (pinfunction "2_2") (pintype "passive"))
    )
    (net (code "37") (name "D2") (class "Default")
      (node (ref "ARD_6") (pin "6") (pinfunction "6_6") (pintype "passive"))
    )
    (net (code "38") (name "D6") (class "Default")
      (node (ref "ARD_6") (pin "2") (pinfunction "2_2") (pintype "passive"))
    )
    (net (code "39") (name "D7") (class "Default")
      (node (ref "ARD_6") (pin "1") (pinfunction "1_1") (pintype "passive"))
    )
    (net (code "40") (name "D22") (class "Default")
      (node (ref "ARD_8") (pin "2") (pinfunction "2_2") (pintype "passive"))
    )
    (net (code "41") (name "D23") (class "Default")
      (node (ref "ARD_9") (pin "2") (pinfunction "2_2") (pintype "passive"))
    )
    (net (code "42") (name "D24") (class "Default")
      (node (ref "ARD_8") (pin "3") (pinfunction "3_3") (pintype "passive"))
    )
    (net (code "43") (name "D25") (class "Default")
      (node (ref "ARD_9") (pin "3") (pinfunction "3_3") (pintype "passive"))
    )
    (net (code "44") (name "D26") (class "Default")
      (node (ref "ARD_8") (pin "4") (pinfunction "4_4") (pintype "passive"))
    )
    (net (code "45") (name "D27") (class "Default")
      (node (ref "ARD_9") (pin "4") (pinfunction "4_4") (pintype "passive"))
    )
    (net (code "46") (name "D29") (class "Default")
      (node (ref "ARD_9") (pin "5") (pinfunction "5_5") (pintype "passive"))
    )
    (net (code "47") (name "D30") (class "Default")
      (node (ref "ARD_8") (pin "6") (pinfunction "6_6") (pintype "passive"))
    )
    (net (code "48") (name "D31") (class "Default")
      (node (ref "ARD_9") (pin "6") (pinfunction "6_6") (pintype "passive"))
    )
    (net (code "49") (name "D33") (class "Default")
      (node (ref "ARD_9") (pin "7") (pinfunction "7_7") (pintype "passive"))
    )
    (net (code "50") (name "D35") (class "Default")
      (node (ref "ARD_9") (pin "8") (pinfunction "8_8") (pintype "passive"))
    )
    (net (code "51") (name "D37") (class "Default")
      (node (ref "ARD_9") (pin "9") (pinfunction "9_9") (pintype "passive"))
    )
    (net (code "52") (name "D39") (class "Default")
      (node (ref "ARD_9") (pin "10") (pinfunction "10_10") (pintype "passive"))
    )
    (net (code "53") (name "D40") (class "Default")
      (node (ref "ARD_8") (pin "11") (pinfunction "11_11") (pintype "passive"))
    )
    (net (code "54") (name "D41") (class "Default")
      (node (ref "ARD_9") (pin "11") (pinfunction "11_11") (pintype "passive"))
    )
    (net (code "55") (name "D42") (class "Default")
      (node (ref "ARD_8") (pin "12") (pinfunction "12_12") (pintype "passive"))
    )
    (net (code "56") (name "D43") (class "Default")
      (node (ref "ARD_9") (pin "12") (pinfunction "12_12") (pintype "passive"))
    )
    (net (code "57") (name "D44") (class "Default")
      (node (ref "ARD_8") (pin "13") (pinfunction "13_13") (pintype "passive"))
    )
    (net (code "58") (name "D45") (class "Default")
      (node (ref "ARD_9") (pin "13") (pinfunction "13_13") (pintype "passive"))
    )
    (net (code "59") (name "D46") (class "Default")
      (node (ref "ARD_8") (pin "14") (pinfunction "14_14") (pintype "passive"))
    )
    (net (code "60") (name "D47") (class "Default")
      (node (ref "ARD_9") (pin "14") (pinfunction "14_14") (pintype "passive"))
    )
    (net (code "61") (name "D48") (class "Default")
      (node (ref "ARD_8") (pin "15") (pinfunction "15_15") (pintype "passive"))
    )
    (net (code "62") (name "D49") (class "Default")
      (node (ref "ARD_9") (pin "15") (pinfunction "15_15") (pintype "passive"))
    )
    (net (code "63") (name "D50") (class "Default")
      (node (ref "ARD_8") (pin "16") (pinfunction "16_16") (pintype "passive"))
    )
    (net (code "64") (name "D51") (class "Default")
      (node (ref "ARD_9") (pin "16") (pinfunction "16_16") (pintype "passive"))
    )
    (net (code "65") (name "D52") (class "Default")
      (node (ref "ARD_8") (pin "17") (pinfunction "17_17") (pintype "passive"))
    )
    (net (code "66") (name "D53") (class "Default")
      (node (ref "ARD_9") (pin "17") (pinfunction "17_17") (pintype "passive"))
    )
    (net (code "67") (name "DAC0") (class "Default")
      (node (ref "ARD_3") (pin "5") (pinfunction "5_5") (pintype "passive"))
    )
    (net (code "68") (name "DAC1") (class "Default")
      (node (ref "ARD_3") (pin "6") (pinfunction "6_6") (pintype "passive"))
    )
    (net (code "69") (name "FLT_CMP_TEMP") (class "Default")
      (node (ref "ARD_2") (pin "7") (pinfunction "7_7") (pintype "passive"))
      (node (ref "R26") (pin "1") (pinfunction "1_1") (pintype "passive"))
      (node (ref "R27") (pin "2") (pinfunction "2_2") (pintype "passive"))
    )
    (net (code "70") (name "GND") (class "Default")
      (node (ref "ALT") (pin "3") (pinfunction "3_3") (pintype "passive"))
      (node (ref "ARD_1") (pin "6") (pinfunction "6_6") (pintype "passive"))
      (node (ref "ARD_1") (pin "7") (pinfunction "7_7") (pintype "passive"))
      (node (ref "ARD_7") (pin "4") (pinfunction "4_4") (pintype "passive"))
      (node (ref "ARD_8") (pin "18") (pinfunction "18_18") (pintype "passive"))
      (node (ref "ARD_9") (pin "18") (pinfunction "18_18") (pintype "passive"))
      (node (ref "B1CC") (pin "2") (pinfunction "2_2") (pintype "passive"))
      (node (ref "B2CC") (pin "2") (pinfunction "2_2") (pintype "passive"))
      (node (ref "C1") (pin "2") (pinfunction "2_2") (pintype "passive"))
      (node (ref "C2") (pin "2") (pinfunction "2_2") (pintype "passive"))
      (node (ref "C3") (pin "2") (pinfunction "2_2") (pintype "passive"))
      (node (ref "C4") (pin "2") (pinfunction "2_2") (pintype "passive"))
      (node (ref "C5") (pin "2") (pinfunction "2_2") (pintype "passive"))
      (node (ref "C6") (pin "2") (pinfunction "2_2") (pintype "passive"))
      (node (ref "GPS1") (pin "GND_A") (pinfunction "GND_A_GND_A") (pintype "bidirectional"))
      (node (ref "GPS1") (pin "GND_B") (pinfunction "GND_B_GND_B") (pintype "bidirectional"))
      (node (ref "GYRO") (pin "1") (pinfunction "1_1") (pintype "passive"))
      (node (ref "LCC") (pin "2") (pinfunction "2_2") (pintype "passive"))
      (node (ref "Q1") (pin "E") (pinfunction "E_E") (pintype "passive"))
      (node (ref "Q2") (pin "E") (pinfunction "E_E") (pintype "passive"))
      (node (ref "Q3") (pin "E") (pinfunction "E_E") (pintype "passive"))
      (node (ref "Q4") (pin "E") (pinfunction "E_E") (pintype "passive"))
      (node (ref "Q5") (pin "E") (pinfunction "E_E") (pintype "passive"))
      (node (ref "Q6") (pin "E") (pinfunction "E_E") (pintype "passive"))
      (node (ref "Q7") (pin "E") (pinfunction "E_E") (pintype "passive"))
      (node (ref "R12") (pin "1") (pinfunction "1_1") (pintype "passive"))
      (node (ref "R13") (pin "1") (pinfunction "1_1") (pintype "passive"))
      (node (ref "R15") (pin "1") (pinfunction "1_1") (pintype "passive"))
      (node (ref "R18") (pin "1") (pinfunction "1_1") (pintype "passive"))
      (node (ref "R19") (pin "1") (pinfunction "1_1") (pintype "passive"))
      (node (ref "R23") (pin "1") (pinfunction "1_1") (pintype "passive"))
      (node (ref "R25") (pin "1") (pinfunction "1_1") (pintype "passive"))
      (node (ref "R27") (pin "1") (pinfunction "1_1") (pintype "passive"))
      (node (ref "R3") (pin "1") (pinfunction "1_1") (pintype "passive"))
      (node (ref "R31") (pin "1") (pinfunction "1_1") (pintype "passive"))
      (node (ref "R33") (pin "1") (pinfunction "1_1") (pintype "passive"))
      (node (ref "R36") (pin "1") (pinfunction "1_1") (pintype "passive"))
      (node (ref "R38") (pin "1") (pinfunction "1_1") (pintype "passive"))
      (node (ref "R8") (pin "1") (pinfunction "1_1") (pintype "passive"))
      (node (ref "R9") (pin "1") (pinfunction "1_1") (pintype "passive"))
      (node (ref "RB1") (pin "6") (pinfunction "6_6") (pintype "passive"))
      (node (ref "RB2") (pin "1") (pinfunction "1_1") (pintype "passive"))
      (node (ref "RB2") (pin "8") (pinfunction "8_8") (pintype "passive"))
      (node (ref "SACC") (pin "2") (pinfunction "2_2") (pintype "passive"))
      (node (ref "X10") (pin "2") (pinfunction "2_2") (pintype "passive"))
      (node (ref "X10") (pin "4") (pinfunction "4_4") (pintype "passive"))
      (node (ref "X12") (pin "4") (pinfunction "GND_4") (pintype "power_in"))
      (node (ref "X17") (pin "10") (pinfunction "S_10") (pintype "passive"))
      (node (ref "X17") (pin "6") (pinfunction "S_6") (pintype "passive"))
      (node (ref "X17") (pin "8") (pinfunction "S_8") (pintype "passive"))
      (node (ref "X9") (pin "2") (pinfunction "2_2") (pintype "passive"))
      (node (ref "X9") (pin "4") (pinfunction "4_4") (pintype "passive"))
    )
    (net (code "71") (name "GYRO_AD0") (class "Default")
      (node (ref "GYRO") (pin "9") (pinfunction "9_9") (pintype "passive"))
    )
    (net (code "72") (name "GYRO_CIN") (class "Default")
      (node (ref "GYRO") (pin "8") (pinfunction "8_8") (pintype "passive"))
    )
    (net (code "73") (name "GYRO_COUT") (class "Default")
      (node (ref "GYRO") (pin "7") (pinfunction "7_7") (pintype "passive"))
    )
    (net (code "74") (name "GYRO_ESC") (class "Default")
      (node (ref "GYRO") (pin "6") (pinfunction "6_6") (pintype "passive"))
    )
    (net (code "75") (name "GYRO_ESD") (class "Default")
      (node (ref "GYRO") (pin "5") (pinfunction "5_5") (pintype "passive"))
    )
    (net (code "76") (name "GYRO_FSYNC") (class "Default")
      (node (ref "GYRO") (pin "10") (pinfunction "10_10") (pintype "passive"))
    )
    (net (code "77") (name "GYRO_INT") (class "Default")
      (node (ref "GYRO") (pin "11") (pinfunction "11_11") (pintype "passive"))
    )
    (net (code "78") (name "GYRO_PWR") (class "Default")
      (node (ref "ARD_8") (pin "5") (pinfunction "5_5") (pintype "passive"))
    )
    (net (code "79") (name "HEATER_1_PWR") (class "Default")
      (node (ref "PO4") (pin "1") (pinfunction "P_1") (pintype "passive"))
      (node (ref "X11") (pin "8") (pinfunction "8_8") (pintype "passive"))
      (node (ref "X4") (pin "1") (pinfunction "S_1") (pintype "passive"))
    )
    (net (code "80") (name "HEATER_1_PWR_RTN") (class "Default")
      (node (ref "Q4") (pin "C") (pinfunction "C_C") (pintype "passive"))
      (node (ref "X11") (pin "9") (pinfunction "9_9") (pintype "passive"))
      (node (ref "X4") (pin "2") (pinfunction "S_2") (pintype "passive"))
    )
    (net (code "81") (name "HEATER_2_PWR") (class "Default")
      (node (ref "PO5") (pin "1") (pinfunction "P_1") (pintype "passive"))
      (node (ref "X11") (pin "10") (pinfunction "10_10") (pintype "passive"))
      (node (ref "X5") (pin "1") (pinfunction "S_1") (pintype "passive"))
    )
    (net (code "82") (name "HEATER_2_PWR_RTN") (class "Default")
      (node (ref "Q5") (pin "C") (pinfunction "C_C") (pintype "passive"))
      (node (ref "X11") (pin "11") (pinfunction "11_11") (pintype "passive"))
      (node (ref "X5") (pin "2") (pinfunction "S_2") (pintype "passive"))
    )
    (net (code "83") (name "HEATER_CONTROL_1") (class "Default")
      (node (ref "ARD_7") (pin "10") (pinfunction "10_10") (pintype "passive"))
      (node (ref "R10") (pin "2") (pinfunction "2_2") (pintype "passive"))
    )
    (net (code "84") (name "HEATER_CONTROL_2") (class "Default")
      (node (ref "ARD_6") (pin "3") (pinfunction "3_3") (pintype "passive"))
      (node (ref "R11") (pin "2") (pinfunction "2_2") (pintype "passive"))
    )
    (net (code "85") (name "IOREF") (class "Default")
      (node (ref "ARD_1") (pin "2") (pinfunction "2_2") (pintype "passive"))
    )
    (net (code "86") (name "LI_ION") (class "Default")
      (node (ref "RB2") (pin "7") (pinfunction "7_7") (pintype "passive"))
    )
    (net (code "87") (name "LOAD_IN") (class "Default")
      (node (ref "D1") (pin "C") (pinfunction "C_C") (pintype "passive"))
      (node (ref "D2") (pin "C") (pinfunction "C_C") (pintype "passive"))
      (node (ref "LCC") (pin "6") (pinfunction "6_6") (pintype "passive"))
    )
    (net (code "88") (name "MISO") (class "Default")
      (node (ref "ARD_4") (pin "1") (pinfunction "1_1") (pintype "passive"))
      (node (ref "ARD_7") (pin "6") (pinfunction "6_6") (pintype "passive"))
    )
    (net (code "89") (name "MOSI") (class "Default")
      (node (ref "ARD_4") (pin "4") (pinfunction "4_4") (pintype "passive"))
      (node (ref "ARD_7") (pin "7") (pinfunction "7_7") (pintype "passive"))
    )
    (net (code "90") (name "N$9") (class "Default")
      (node (ref "GYRO") (pin "2") (pinfunction "2_2") (pintype "passive"))
    )
    (net (code "91") (name "N$10") (class "Default")
      (node (ref "ARD_4") (pin "2") (pinfunction "2_2") (pintype "passive"))
    )
    (net (code "92") (name "N$11") (class "Default")
      (node (ref "ARD_4") (pin "6") (pinfunction "6_6") (pintype "passive"))
    )
    (net (code "93") (name "N$14") (class "Default")
      (node (ref "ARD_4") (pin "5") (pinfunction "5_5") (pintype "passive"))
    )
    (net (code "94") (name "NET_AV") (class "Default")
      (node (ref "RB2") (pin "5") (pinfunction "5_5") (pintype "passive"))
    )
    (net (code "95") (name "Net-(B1_CELL_1-P)") (class "Default")
      (node (ref "B1_CELL_1") (pin "1") (pinfunction "P_1") (pintype "passive"))
      (node (ref "X13") (pin "5") (pinfunction "S_5") (pintype "passive"))
    )
    (net (code "96") (name "Net-(B1_CELL_2-P)") (class "Default")
      (node (ref "B1_CELL_2") (pin "1") (pinfunction "P_1") (pintype "passive"))
      (node (ref "X13") (pin "4") (pinfunction "S_4") (pintype "passive"))
    )
    (net (code "97") (name "Net-(B1_CELL_3-P)") (class "Default")
      (node (ref "B1_CELL_3") (pin "1") (pinfunction "P_1") (pintype "passive"))
      (node (ref "X13") (pin "3") (pinfunction "S_3") (pintype "passive"))
    )
    (net (code "98") (name "Net-(B2_CELL_1-P)") (class "Default")
      (node (ref "B2_CELL_1") (pin "1") (pinfunction "P_1") (pintype "passive"))
      (node (ref "X14") (pin "5") (pinfunction "S_5") (pintype "passive"))
    )
    (net (code "99") (name "Net-(B2_CELL_2-P)") (class "Default")
      (node (ref "B2_CELL_2") (pin "1") (pinfunction "P_1") (pintype "passive"))
      (node (ref "X14") (pin "4") (pinfunction "S_4") (pintype "passive"))
    )
    (net (code "100") (name "Net-(B3_CELL_3-P)") (class "Default")
      (node (ref "B3_CELL_3") (pin "1") (pinfunction "P_1") (pintype "passive"))
      (node (ref "X14") (pin "3") (pinfunction "S_3") (pintype "passive"))
    )
    (net (code "101") (name "Net-(GPS1-PadRESET)") (class "Default")
      (node (ref "GPS1") (pin "RESET") (pinfunction "RESET_RESET") (pintype "bidirectional"))
      (node (ref "R34") (pin "2") (pinfunction "2_2") (pintype "passive"))
    )
    (net (code "102") (name "Net-(GPS1-PadRXA)") (class "Default")
      (node (ref "GPS1") (pin "RXA") (pinfunction "RXA_RXA") (pintype "bidirectional"))
      (node (ref "R29") (pin "2") (pinfunction "2_2") (pintype "passive"))
    )
    (net (code "103") (name "Net-(GPS1-PadRXB)") (class "Default")
      (node (ref "GPS1") (pin "RXB") (pinfunction "RXB_RXB") (pintype "bidirectional"))
      (node (ref "R28") (pin "2") (pinfunction "2_2") (pintype "passive"))
    )
    (net (code "104") (name "Net-(GPS1-PadTXA)") (class "Default")
      (node (ref "GPS1") (pin "TXA") (pinfunction "TXA_TXA") (pintype "bidirectional"))
      (node (ref "R20") (pin "1") (pinfunction "1_1") (pintype "passive"))
    )
    (net (code "105") (name "Net-(GPS1-PadTXB)") (class "Default")
      (node (ref "GPS1") (pin "TXB") (pinfunction "TXB_TXB") (pintype "bidirectional"))
      (node (ref "R21") (pin "1") (pinfunction "1_1") (pintype "passive"))
    )
    (net (code "106") (name "Net-(Q4-PadB)") (class "Default")
      (node (ref "Q4") (pin "B") (pinfunction "B_B") (pintype "passive"))
      (node (ref "R10") (pin "1") (pinfunction "1_1") (pintype "passive"))
      (node (ref "R12") (pin "2") (pinfunction "2_2") (pintype "passive"))
    )
    (net (code "107") (name "Net-(Q5-PadB)") (class "Default")
      (node (ref "Q5") (pin "B") (pinfunction "B_B") (pintype "passive"))
      (node (ref "R11") (pin "1") (pinfunction "1_1") (pintype "passive"))
      (node (ref "R13") (pin "2") (pinfunction "2_2") (pintype "passive"))
    )
    (net (code "108") (name "Net-(Q6-PadB)") (class "Default")
      (node (ref "Q6") (pin "B") (pinfunction "B_B") (pintype "passive"))
      (node (ref "R16") (pin "1") (pinfunction "1_1") (pintype "passive"))
      (node (ref "R18") (pin "2") (pinfunction "2_2") (pintype "passive"))
    )
    (net (code "109") (name "Net-(Q7-PadB)") (class "Default")
      (node (ref "Q7") (pin "B") (pinfunction "B_B") (pintype "passive"))
      (node (ref "R17") (pin "1") (pinfunction "1_1") (pintype "passive"))
      (node (ref "R19") (pin "2") (pinfunction "2_2") (pintype "passive"))
    )
    (net (code "110") (name "Net-(T1-B)") (class "Default")
      (node (ref "R1") (pin "1") (pinfunction "1_1") (pintype "passive"))
      (node (ref "R2") (pin "2") (pinfunction "2_2") (pintype "passive"))
      (node (ref "T1") (pin "2") (pinfunction "B_2") (pintype "passive"))
    )
    (net (code "111") (name "Net-(T1-E)") (class "Default")
      (node (ref "Q1") (pin "B") (pinfunction "B_B") (pintype "passive"))
      (node (ref "R2") (pin "1") (pinfunction "1_1") (pintype "passive"))
      (node (ref "R3") (pin "2") (pinfunction "2_2") (pintype "passive"))
      (node (ref "T1") (pin "3") (pinfunction "E_3") (pintype "passive"))
    )
    (net (code "112") (name "Net-(T2-B)") (class "Default")
      (node (ref "R4") (pin "1") (pinfunction "1_1") (pintype "passive"))
      (node (ref "R6") (pin "2") (pinfunction "2_2") (pintype "passive"))
      (node (ref "T2") (pin "2") (pinfunction "B_2") (pintype "passive"))
    )
    (net (code "113") (name "Net-(T2-E)") (class "Default")
      (node (ref "Q2") (pin "B") (pinfunction "B_B") (pintype "passive"))
      (node (ref "R6") (pin "1") (pinfunction "1_1") (pintype "passive"))
      (node (ref "R8") (pin "2") (pinfunction "2_2") (pintype "passive"))
      (node (ref "T2") (pin "3") (pinfunction "E_3") (pintype "passive"))
    )
    (net (code "114") (name "Net-(T3-B)") (class "Default")
      (node (ref "R5") (pin "1") (pinfunction "1_1") (pintype "passive"))
      (node (ref "R7") (pin "2") (pinfunction "2_2") (pintype "passive"))
      (node (ref "T3") (pin "2") (pinfunction "B_2") (pintype "passive"))
    )
    (net (code "115") (name "Net-(T3-E)") (class "Default")
      (node (ref "Q3") (pin "B") (pinfunction "B_B") (pintype "passive"))
      (node (ref "R7") (pin "1") (pinfunction "1_1") (pintype "passive"))
      (node (ref "R9") (pin "2") (pinfunction "2_2") (pintype "passive"))
      (node (ref "T3") (pin "3") (pinfunction "E_3") (pintype "passive"))
    )
    (net (code "116") (name "ON_OFF") (class "Default")
      (node (ref "RB2") (pin "6") (pinfunction "6_6") (pintype "passive"))
    )
    (net (code "117") (name "PYRO_1_PWR") (class "Default")
      (node (ref "PO1") (pin "1") (pinfunction "P_1") (pintype "passive"))
      (node (ref "X11") (pin "1") (pinfunction "1_1") (pintype "passive"))
      (node (ref "X2") (pin "1") (pinfunction "S_1") (pintype "passive"))
    )
    (net (code "118") (name "PYRO_1_PWR_RTN") (class "Default")
      (node (ref "Q1") (pin "C") (pinfunction "C_C") (pintype "passive"))
      (node (ref "T1") (pin "1") (pinfunction "C_1") (pintype "passive"))
      (node (ref "X11") (pin "2") (pinfunction "2_2") (pintype "passive"))
      (node (ref "X2") (pin "2") (pinfunction "S_2") (pintype "passive"))
    )
    (net (code "119") (name "PYRO_2_PWR") (class "Default")
      (node (ref "PO2") (pin "1") (pinfunction "P_1") (pintype "passive"))
      (node (ref "X1") (pin "1") (pinfunction "S_1") (pintype "passive"))
      (node (ref "X11") (pin "3") (pinfunction "3_3") (pintype "passive"))
    )
    (net (code "120") (name "PYRO_2_PWR_RTN") (class "Default")
      (node (ref "Q2") (pin "C") (pinfunction "C_C") (pintype "passive"))
      (node (ref "T2") (pin "1") (pinfunction "C_1") (pintype "passive"))
      (node (ref "X1") (pin "2") (pinfunction "S_2") (pintype "passive"))
      (node (ref "X11") (pin "4") (pinfunction "4_4") (pintype "passive"))
    )
    (net (code "121") (name "RESET") (class "Default")
      (node (ref "ARD_1") (pin "3") (pinfunction "3_3") (pintype "passive"))
      (node (ref "X17") (pin "9") (pinfunction "S_9") (pintype "passive"))
    )
    (net (code "122") (name "RF_IN") (class "Default")
      (node (ref "GPS1") (pin "RF_IN") (pinfunction "RF_IN_RF_IN") (pintype "bidirectional"))
      (node (ref "L1") (pin "1") (pinfunction "1_1") (pintype "passive"))
    )
    (net (code "123") (name "RI") (class "Default")
      (node (ref "RB2") (pin "4") (pinfunction "4_4") (pintype "passive"))
    )
    (net (code "124") (name "RX0") (class "Default")
      (node (ref "ARD_6") (pin "8") (pinfunction "8_8") (pintype "passive"))
      (node (ref "X12") (pin "2") (pinfunction "D-_2") (pintype "bidirectional"))
    )
    (net (code "125") (name "RX1") (class "Default")
      (node (ref "ARD_5") (pin "6") (pinfunction "6_6") (pintype "passive"))
      (node (ref "C6") (pin "1") (pinfunction "1_1") (pintype "passive"))
      (node (ref "R29") (pin "1") (pinfunction "1_1") (pintype "passive"))
    )
    (net (code "126") (name "RX2") (class "Default")
      (node (ref "ARD_5") (pin "4") (pinfunction "4_4") (pintype "passive"))
    )
    (net (code "127") (name "RX3") (class "Default")
      (node (ref "ARD_5") (pin "2") (pinfunction "2_2") (pintype "passive"))
      (node (ref "RB1") (pin "2") (pinfunction "2_2") (pintype "passive"))
    )
    (net (code "128") (name "RXB") (class "Default")
      (node (ref "C5") (pin "1") (pinfunction "1_1") (pintype "passive"))
      (node (ref "R28") (pin "1") (pinfunction "1_1") (pintype "passive"))
    )
    (net (code "129") (name "SCK") (class "Default")
      (node (ref "ARD_4") (pin "3") (pinfunction "3_3") (pintype "passive"))
      (node (ref "ARD_7") (pin "5") (pinfunction "5_5") (pintype "passive"))
    )
    (net (code "130") (name "SCL") (class "Default")
      (node (ref "ARD_5") (pin "8") (pinfunction "8_8") (pintype "passive"))
      (node (ref "B1CC") (pin "3") (pinfunction "3_3") (pintype "passive"))
      (node (ref "B2CC") (pin "3") (pinfunction "3_3") (pintype "passive"))
      (node (ref "GYRO") (pin "4") (pinfunction "4_4") (pintype "passive"))
      (node (ref "LCC") (pin "3") (pinfunction "3_3") (pintype "passive"))
      (node (ref "SACC") (pin "3") (pinfunction "3_3") (pintype "passive"))
    )
    (net (code "131") (name "SCL1") (class "Default")
      (node (ref "ARD_7") (pin "1") (pinfunction "1_1") (pintype "passive"))
    )
    (net (code "132") (name "SDA") (class "Default")
      (node (ref "ARD_5") (pin "7") (pinfunction "7_7") (pintype "passive"))
      (node (ref "B1CC") (pin "4") (pinfunction "4_4") (pintype "passive"))
      (node (ref "B2CC") (pin "4") (pinfunction "4_4") (pintype "passive"))
      (node (ref "GYRO") (pin "3") (pinfunction "3_3") (pintype "passive"))
      (node (ref "LCC") (pin "4") (pinfunction "4_4") (pintype "passive"))
      (node (ref "SACC") (pin "4") (pinfunction "4_4") (pintype "passive"))
    )
    (net (code "133") (name "SDA1") (class "Default")
      (node (ref "ARD_7") (pin "2") (pinfunction "2_2") (pintype "passive"))
    )
    (net (code "134") (name "SPARE_1_PWR") (class "Default")
      (node (ref "PO6") (pin "1") (pinfunction "P_1") (pintype "passive"))
      (node (ref "X11") (pin "12") (pinfunction "12_12") (pintype "passive"))
      (node (ref "X6") (pin "1") (pinfunction "S_1") (pintype "passive"))
    )
    (net (code "135") (name "SPARE_1_PWR_RTN") (class "Default")
      (node (ref "Q6") (pin "C") (pinfunction "C_C") (pintype "passive"))
      (node (ref "X11") (pin "13") (pinfunction "13_13") (pintype "passive"))
      (node (ref "X6") (pin "2") (pinfunction "S_2") (pintype "passive"))
    )
    (net (code "136") (name "SPARE_2_PWR") (class "Default")
      (node (ref "PO7") (pin "1") (pinfunction "P_1") (pintype "passive"))
      (node (ref "X11") (pin "14") (pinfunction "14_14") (pintype "passive"))
      (node (ref "X7") (pin "1") (pinfunction "S_1") (pintype "passive"))
    )
    (net (code "137") (name "SPARE_2_PWR_RTN") (class "Default")
      (node (ref "Q7") (pin "C") (pinfunction "C_C") (pintype "passive"))
      (node (ref "X11") (pin "15") (pinfunction "15_15") (pintype "passive"))
      (node (ref "X7") (pin "2") (pinfunction "S_2") (pintype "passive"))
    )
    (net (code "138") (name "SPARE_HIGH_1_CONTROL") (class "Default")
      (node (ref "R5") (pin "2") (pinfunction "2_2") (pintype "passive"))
    )
    (net (code "139") (name "SPARE_HIGH_1_PWR") (class "Default")
      (node (ref "PO3") (pin "1") (pinfunction "P_1") (pintype "passive"))
      (node (ref "X11") (pin "5") (pinfunction "5_5") (pintype "passive"))
      (node (ref "X3") (pin "1") (pinfunction "S_1") (pintype "passive"))
    )
    (net (code "140") (name "SPARE_HIGH_1_PWR_RTN") (class "Default")
      (node (ref "Q3") (pin "C") (pinfunction "C_C") (pintype "passive"))
      (node (ref "T3") (pin "1") (pinfunction "C_1") (pintype "passive"))
      (node (ref "X11") (pin "6") (pinfunction "6_6") (pintype "passive"))
      (node (ref "X3") (pin "2") (pinfunction "S_2") (pintype "passive"))
    )
    (net (code "141") (name "SPARE_LOW_1_CONTROL_1") (class "Default")
      (node (ref "R16") (pin "2") (pinfunction "2_2") (pintype "passive"))
    )
    (net (code "142") (name "SPARE_LOW_2_CONTROL") (class "Default")
      (node (ref "R17") (pin "2") (pinfunction "2_2") (pintype "passive"))
    )
    (net (code "143") (name "S{slash}A_PWR_IN") (class "Default")
      (node (ref "SACC") (pin "6") (pinfunction "6_6") (pintype "passive"))
      (node (ref "X10") (pin "10") (pinfunction "10_10") (pintype "passive"))
      (node (ref "X10") (pin "6") (pinfunction "6_6") (pintype "passive"))
      (node (ref "X10") (pin "8") (pinfunction "8_8") (pintype "passive"))
    )
    (net (code "144") (name "S{slash}A_PWR_OUT") (class "Default")
      (node (ref "SACC") (pin "5") (pinfunction "5_5") (pintype "passive"))
      (node (ref "X15") (pin "3") (pinfunction "S_3") (pintype "passive"))
    )
    (net (code "145") (name "S{slash}A_PWR_RTN") (class "Default")
      (node (ref "X10") (pin "11") (pinfunction "11_11") (pintype "passive"))
      (node (ref "X10") (pin "7") (pinfunction "7_7") (pintype "passive"))
      (node (ref "X10") (pin "9") (pinfunction "9_9") (pintype "passive"))
      (node (ref "X15") (pin "4") (pinfunction "S_4") (pintype "passive"))
    )
    (net (code "146") (name "TEMP_EXT_1") (class "Default")
      (node (ref "ARD_2") (pin "8") (pinfunction "8_8") (pintype "passive"))
      (node (ref "R22") (pin "1") (pinfunction "1_1") (pintype "passive"))
      (node (ref "R23") (pin "2") (pinfunction "2_2") (pintype "passive"))
      (node (ref "X9") (pin "1") (pinfunction "1_1") (pintype "passive"))
    )
    (net (code "147") (name "TEMP_EXT_2") (class "Default")
      (node (ref "ARD_2") (pin "6") (pinfunction "6_6") (pintype "passive"))
      (node (ref "R24") (pin "1") (pinfunction "1_1") (pintype "passive"))
      (node (ref "R25") (pin "2") (pinfunction "2_2") (pintype "passive"))
      (node (ref "X9") (pin "3") (pinfunction "3_3") (pintype "passive"))
    )
    (net (code "148") (name "TX0") (class "Default")
      (node (ref "ARD_6") (pin "7") (pinfunction "7_7") (pintype "passive"))
      (node (ref "X12") (pin "3") (pinfunction "D+_3") (pintype "bidirectional"))
    )
    (net (code "149") (name "TX1") (class "Default")
      (node (ref "ARD_5") (pin "5") (pinfunction "5_5") (pintype "passive"))
      (node (ref "C2") (pin "1") (pinfunction "1_1") (pintype "passive"))
      (node (ref "R20") (pin "2") (pinfunction "2_2") (pintype "passive"))
    )
    (net (code "150") (name "TX2") (class "Default")
      (node (ref "ARD_5") (pin "3") (pinfunction "3_3") (pintype "passive"))
    )
    (net (code "151") (name "TX3") (class "Default")
      (node (ref "ARD_5") (pin "1") (pinfunction "1_1") (pintype "passive"))
      (node (ref "RB1") (pin "3") (pinfunction "3_3") (pintype "passive"))
    )
    (net (code "152") (name "TXB") (class "Default")
      (node (ref "C4") (pin "1") (pinfunction "1_1") (pintype "passive"))
      (node (ref "R21") (pin "2") (pinfunction "2_2") (pintype "passive"))
    )
    (net (code "153") (name "UNKNOWN") (class "Default")
      (node (ref "ARD_1") (pin "1") (pinfunction "1_1") (pintype "passive"))
    )
    (net (code "154") (name "VBAT") (class "Default")
      (node (ref "GPS1") (pin "VBAT") (pinfunction "VBAT_VBAT") (pintype "bidirectional"))
    )
    (net (code "155") (name "VCC_RB") (class "Default")
      (node (ref "RB1") (pin "4") (pinfunction "4_4") (pintype "passive"))
    )
    (net (code "156") (name "VIN") (class "Default")
      (node (ref "ARD_1") (pin "8") (pinfunction "8_8") (pintype "passive"))
      (node (ref "LCC") (pin "5") (pinfunction "5_5") (pintype "passive"))
      (node (ref "PVIN1") (pin "1") (pinfunction "P_1") (pintype "passive"))
      (node (ref "PVIN2") (pin "1") (pinfunction "P_1") (pintype "passive"))
      (node (ref "PVIN3") (pin "1") (pinfunction "P_1") (pintype "passive"))
      (node (ref "PVIN4") (pin "1") (pinfunction "P_1") (pintype "passive"))
      (node (ref "PVIN5") (pin "1") (pinfunction "P_1") (pintype "passive"))
      (node (ref "PVIN6") (pin "1") (pinfunction "P_1") (pintype "passive"))
      (node (ref "PVIN7") (pin "1") (pinfunction "P_1") (pintype "passive"))
      (node (ref "R14") (pin "2") (pinfunction "2_2") (pintype "passive"))
    )
    (net (code "157") (name "VIN_VOLTAGE_TLM") (class "Default")
      (node (ref "ARD_2") (pin "4") (pinfunction "4_4") (pintype "passive"))
      (node (ref "C1") (pin "1") (pinfunction "1_1") (pintype "passive"))
      (node (ref "R14") (pin "1") (pinfunction "1_1") (pintype "passive"))
      (node (ref "R15") (pin "2") (pinfunction "2_2") (pintype "passive"))
    )
    (net (code "158") (name "unconnected-(ALT-Pad8)") (class "Default")
      (node (ref "ALT") (pin "8") (pinfunction "8_8") (pintype "passive"))
    )
    (net (code "159") (name "unconnected-(GPS1-GBIO_15-PadGPIO_15)") (class "Default")
      (node (ref "GPS1") (pin "GPIO_15") (pinfunction "GBIO_15_GPIO_15") (pintype "bidirectional"))
    )
    (net (code "160") (name "unconnected-(GPS1-PadBOOT_SEL)") (class "Default")
      (node (ref "GPS1") (pin "BOOT_SEL") (pinfunction "BOOT_SEL_BOOT_SEL") (pintype "bidirectional"))
    )
    (net (code "161") (name "unconnected-(GPS1-PadGPIO_01)") (class "Default")
      (node (ref "GPS1") (pin "GPIO_01") (pinfunction "GPIO_01_GPIO_01") (pintype "bidirectional"))
    )
    (net (code "162") (name "unconnected-(GPS1-PadGPIO_13)") (class "Default")
      (node (ref "GPS1") (pin "GPIO_13") (pinfunction "GPIO_13_GPIO_13") (pintype "bidirectional"))
    )
    (net (code "163") (name "unconnected-(GPS1-PadGPIO_14)") (class "Default")
      (node (ref "GPS1") (pin "GPIO_14") (pinfunction "GPIO_14_GPIO_14") (pintype "bidirectional"))
    )
    (net (code "164") (name "unconnected-(GPS1-PadON_OFF)") (class "Default")
      (node (ref "GPS1") (pin "ON_OFF") (pinfunction "ON_OFF_ON_OFF") (pintype "bidirectional"))
    )
    (net (code "165") (name "unconnected-(GPS1-PadPWR_CHK)") (class "Default")
      (node (ref "GPS1") (pin "PWR_CHK") (pinfunction "PWR_CHK_PWR_CHK") (pintype "bidirectional"))
    )
    (net (code "166") (name "unconnected-(GPS1-PadTIMEMARK)") (class "Default")
      (node (ref "GPS1") (pin "TIMEMARK") (pinfunction "TIMEMARK_TIMEMARK") (pintype "bidirectional"))
    )
    (net (code "167") (name "unconnected-(GYRO-Pad12)") (class "Default")
      (node (ref "GYRO") (pin "12") (pinfunction "12_12") (pintype "passive"))
    )
    (net (code "168") (name "unconnected-(X9-Pad5)") (class "Default")
      (node (ref "X9") (pin "5") (pinfunction "5_5") (pintype "passive"))
    )
    (net (code "169") (name "unconnected-(X9-Pad6)") (class "Default")
      (node (ref "X9") (pin "6") (pinfunction "6_6") (pintype "passive"))
    )
    (net (code "170") (name "unconnected-(X9-Pad7)") (class "Default")
      (node (ref "X9") (pin "7") (pinfunction "7_7") (pintype "passive"))
    )
    (net (code "171") (name "unconnected-(X9-Pad8)") (class "Default")
      (node (ref "X9") (pin "8") (pinfunction "8_8") (pintype "passive"))
    )
    (net (code "172") (name "unconnected-(X9-Pad9)") (class "Default")
      (node (ref "X9") (pin "9") (pinfunction "9_9") (pintype "passive"))
    )
    (net (code "173") (name "unconnected-(X9-Pad10)") (class "Default")
      (node (ref "X9") (pin "10") (pinfunction "10_10") (pintype "passive"))
    )
    (net (code "174") (name "unconnected-(X9-Pad11)") (class "Default")
      (node (ref "X9") (pin "11") (pinfunction "11_11") (pintype "passive"))
    )
    (net (code "175") (name "unconnected-(X9-Pad12)") (class "Default")
      (node (ref "X9") (pin "12") (pinfunction "12_12") (pintype "passive"))
    )
    (net (code "176") (name "unconnected-(X9-Pad13)") (class "Default")
      (node (ref "X9") (pin "13") (pinfunction "13_13") (pintype "passive"))
    )
    (net (code "177") (name "unconnected-(X9-Pad14)") (class "Default")
      (node (ref "X9") (pin "14") (pinfunction "14_14") (pintype "passive"))
    )
    (net (code "178") (name "unconnected-(X9-Pad15)") (class "Default")
      (node (ref "X9") (pin "15") (pinfunction "15_15") (pintype "passive"))
    )
    (net (code "179") (name "unconnected-(X10-Pad5)") (class "Default")
      (node (ref "X10") (pin "5") (pinfunction "5_5") (pintype "passive"))
    )
    (net (code "180") (name "unconnected-(X10-Pad12)") (class "Default")
      (node (ref "X10") (pin "12") (pinfunction "12_12") (pintype "passive"))
    )
    (net (code "181") (name "unconnected-(X10-Pad13)") (class "Default")
      (node (ref "X10") (pin "13") (pinfunction "13_13") (pintype "passive"))
    )
    (net (code "182") (name "unconnected-(X10-Pad14)") (class "Default")
      (node (ref "X10") (pin "14") (pinfunction "14_14") (pintype "passive"))
    )
    (net (code "183") (name "unconnected-(X10-Pad15)") (class "Default")
      (node (ref "X10") (pin "15") (pinfunction "15_15") (pintype "passive"))
    )
    (net (code "184") (name "unconnected-(X11-Pad7)") (class "Default")
      (node (ref "X11") (pin "7") (pinfunction "7_7") (pintype "passive"))
    )
    (net (code "185") (name "unconnected-(X13B-S-Pad2)") (class "Default")
      (node (ref "X13") (pin "2") (pinfunction "S_2") (pintype "passive"))
    )
    (net (code "186") (name "unconnected-(X14B-S-Pad2)") (class "Default")
      (node (ref "X14") (pin "2") (pinfunction "S_2") (pintype "passive"))
    )
  )
)
